# xbee_2017_v2.net
KiCad netlist of a schematic drawn in EAGLE
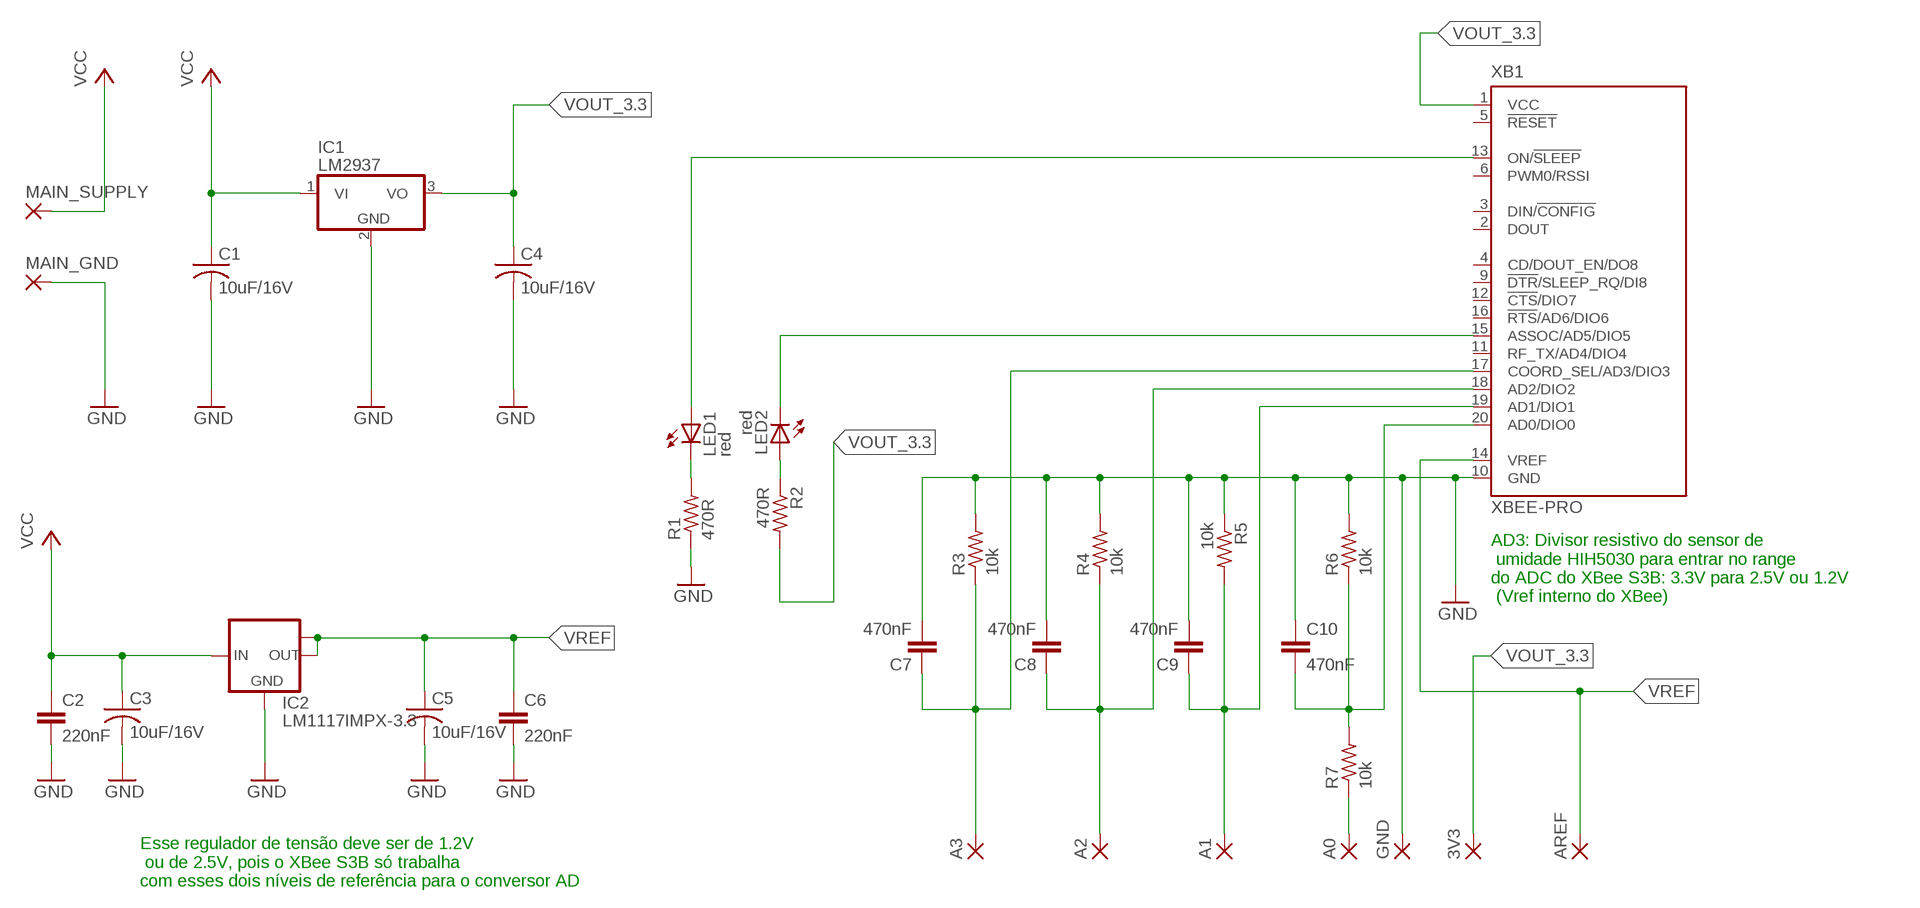
[diagram p0: schematic, sheet 1]

(export (version "E")
  (design (tool "Eeschema 10.0.6"))
  (components
    (comp (ref "3V3")
      (value "2,54/0,9")
      (footprint "eagle-import:2,54_0,9")
      (libsource (lib "eagle-import") (part "2,54/0,9"))
    )
    (comp (ref "A0")
      (value "2,54/0,9")
      (footprint "eagle-import:2,54_0,9")
      (libsource (lib "eagle-import") (part "2,54/0,9"))
    )
    (comp (ref "A1")
      (value "2,54/0,9")
      (footprint "eagle-import:2,54_0,9")
      (libsource (lib "eagle-import") (part "2,54/0,9"))
    )
    (comp (ref "A2")
      (value "2,54/0,9")
      (footprint "eagle-import:2,54_0,9")
      (libsource (lib "eagle-import") (part "2,54/0,9"))
    )
    (comp (ref "A3")
      (value "2,54/0,9")
      (footprint "eagle-import:2,54_0,9")
      (libsource (lib "eagle-import") (part "2,54/0,9"))
    )
    (comp (ref "AREF")
      (value "2,54/0,9")
      (footprint "eagle-import:2,54_0,9")
      (libsource (lib "eagle-import") (part "2,54/0,9"))
    )
    (comp (ref "C1")
      (value "10uF/16V")
      (footprint "eagle-import:C025-030X050")
      (libsource (lib "eagle-import") (part "C-US025-030X050"))
    )
    (comp (ref "C2")
      (value "220nF")
      (footprint "eagle-import:C025-025X050")
      (libsource (lib "eagle-import") (part "C-EU025-025X050"))
    )
    (comp (ref "C3")
      (value "10uF/16V")
      (footprint "eagle-import:C025-030X050")
      (libsource (lib "eagle-import") (part "C-US025-030X050"))
    )
    (comp (ref "C4")
      (value "10uF/16V")
      (footprint "eagle-import:C025-030X050")
      (libsource (lib "eagle-import") (part "C-US025-030X050"))
    )
    (comp (ref "C5")
      (value "10uF/16V")
      (footprint "eagle-import:C025-030X050")
      (libsource (lib "eagle-import") (part "C-US025-030X050"))
    )
    (comp (ref "C6")
      (value "220nF")
      (footprint "eagle-import:C025-025X050")
      (libsource (lib "eagle-import") (part "C-EU025-025X050"))
    )
    (comp (ref "C7")
      (value "470nF")
      (footprint "eagle-import:C5B2.5")
      (libsource (lib "eagle-import") (part "C5/2.5"))
    )
    (comp (ref "C8")
      (value "470nF")
      (footprint "eagle-import:C5B2.5")
      (libsource (lib "eagle-import") (part "C5/2.5"))
    )
    (comp (ref "C9")
      (value "470nF")
      (footprint "eagle-import:C5B2.5")
      (libsource (lib "eagle-import") (part "C5/2.5"))
    )
    (comp (ref "C10")
      (value "470nF")
      (footprint "eagle-import:C5B2.5")
      (libsource (lib "eagle-import") (part "C5/2.5"))
    )
    (comp (ref "GND")
      (value "2,54/0,9")
      (footprint "eagle-import:2,54_0,9")
      (libsource (lib "eagle-import") (part "2,54/0,9"))
    )
    (comp (ref "IC1")
      (value "LM2937")
      (footprint "eagle-import:TO263-3")
      (libsource (lib "eagle-import") (part "LM2937"))
    )
    (comp (ref "IC2")
      (value "LM1117IMPX-3.3")
      (footprint "eagle-import:SOT223")
      (libsource (lib "eagle-import") (part "LM1117IMPX-3.3"))
    )
    (comp (ref "LED1")
      (value "red")
      (footprint "eagle-import:LED3MM")
      (libsource (lib "eagle-import") (part "LED3MM"))
    )
    (comp (ref "LED2")
      (value "red")
      (footprint "eagle-import:LED3MM")
      (libsource (lib "eagle-import") (part "LED3MM"))
    )
    (comp (ref "MAIN_GND")
      (value "3,17/1,3")
      (footprint "eagle-import:3,17_1,3")
      (libsource (lib "eagle-import") (part "3,17/1,3"))
    )
    (comp (ref "MAIN_SUPPLY")
      (value "3,17/1,3")
      (footprint "eagle-import:3,17_1,3")
      (libsource (lib "eagle-import") (part "3,17/1,3"))
    )
    (comp (ref "R1")
      (value "470R")
      (footprint "eagle-import:0207_10")
      (libsource (lib "eagle-import") (part "R-US_0207/10"))
    )
    (comp (ref "R2")
      (value "470R")
      (footprint "eagle-import:0207_10")
      (libsource (lib "eagle-import") (part "R-US_0207/10"))
    )
    (comp (ref "R3")
      (value "10k")
      (footprint "eagle-import:0207_10")
      (libsource (lib "eagle-import") (part "R-US_0207/10"))
    )
    (comp (ref "R4")
      (value "10k")
      (footprint "eagle-import:0207_10")
      (libsource (lib "eagle-import") (part "R-US_0207/10"))
    )
    (comp (ref "R5")
      (value "10k")
      (footprint "eagle-import:0207_10")
      (libsource (lib "eagle-import") (part "R-US_0207/10"))
    )
    (comp (ref "R6")
      (value "10k")
      (footprint "eagle-import:0207_10")
      (libsource (lib "eagle-import") (part "R-US_0207/10"))
    )
    (comp (ref "R7")
      (value "10k")
      (footprint "eagle-import:0207_10")
      (libsource (lib "eagle-import") (part "R-US_0207/10"))
    )
    (comp (ref "XB1")
      (value "XBEE-PRO")
      (footprint "eagle-import:XBEE-PRO")
      (fields (field (name "MPN") "XBP24-AWI-001"))
      (libsource (lib "eagle-import") (part "XBEE-PRO"))
    )
  )
  (nets
    (net (code "1") (name "GND") (class "Default")
      (node (ref "C1") (pin "2") (pinfunction "2_2") (pintype "passive"))
      (node (ref "C10") (pin "1") (pinfunction "1_1") (pintype "passive"))
      (node (ref "C2") (pin "2") (pinfunction "2_2") (pintype "passive"))
      (node (ref "C3") (pin "2") (pinfunction "2_2") (pintype "passive"))
      (node (ref "C4") (pin "2") (pinfunction "2_2") (pintype "passive"))
      (node (ref "C5") (pin "2") (pinfunction "2_2") (pintype "passive"))
      (node (ref "C6") (pin "2") (pinfunction "2_2") (pintype "passive"))
      (node (ref "C7") (pin "2") (pinfunction "2_2") (pintype "passive"))
      (node (ref "C8") (pin "2") (pinfunction "2_2") (pintype "passive"))
      (node (ref "C9") (pin "2") (pinfunction "2_2") (pintype "passive"))
      (node (ref "GND") (pin "1") (pinfunction "P_1") (pintype "passive"))
      (node (ref "IC1") (pin "2") (pinfunction "GND_2") (pintype "passive"))
      (node (ref "IC2") (pin "1") (pinfunction "GND_1") (pintype "input"))
      (node (ref "MAIN_GND") (pin "1") (pinfunction "P_1") (pintype "passive"))
      (node (ref "R1") (pin "1") (pinfunction "1_1") (pintype "passive"))
      (node (ref "R3") (pin "2") (pinfunction "2_2") (pintype "passive"))
      (node (ref "R4") (pin "2") (pinfunction "2_2") (pintype "passive"))
      (node (ref "R5") (pin "1") (pinfunction "1_1") (pintype "passive"))
      (node (ref "R6") (pin "2") (pinfunction "2_2") (pintype "passive"))
      (node (ref "XB1") (pin "10") (pinfunction "GND_10") (pintype "power_in"))
    )
    (net (code "2") (name "Net-(A0-P)") (class "Default")
      (node (ref "A0") (pin "1") (pinfunction "P_1") (pintype "passive"))
      (node (ref "R7") (pin "1") (pinfunction "1_1") (pintype "passive"))
    )
    (net (code "3") (name "Net-(A1-P)") (class "Default")
      (node (ref "A1") (pin "1") (pinfunction "P_1") (pintype "passive"))
      (node (ref "C9") (pin "1") (pinfunction "1_1") (pintype "passive"))
      (node (ref "R5") (pin "2") (pinfunction "2_2") (pintype "passive"))
      (node (ref "XB1") (pin "19") (pinfunction "AD1/DIO1_19") (pintype "bidirectional"))
    )
    (net (code "4") (name "Net-(A2-P)") (class "Default")
      (node (ref "A2") (pin "1") (pinfunction "P_1") (pintype "passive"))
      (node (ref "C8") (pin "1") (pinfunction "1_1") (pintype "passive"))
      (node (ref "R4") (pin "1") (pinfunction "1_1") (pintype "passive"))
      (node (ref "XB1") (pin "18") (pinfunction "AD2/DIO2_18") (pintype "bidirectional"))
    )
    (net (code "5") (name "Net-(A3-P)") (class "Default")
      (node (ref "A3") (pin "1") (pinfunction "P_1") (pintype "passive"))
      (node (ref "C7") (pin "1") (pinfunction "1_1") (pintype "passive"))
      (node (ref "R3") (pin "1") (pinfunction "1_1") (pintype "passive"))
      (node (ref "XB1") (pin "17") (pinfunction "COORD_SEL/AD3/DIO3_17") (pintype "bidirectional"))
    )
    (net (code "6") (name "Net-(LED1-C)") (class "Default")
      (node (ref "LED1") (pin "K") (pinfunction "C_K") (pintype "passive"))
      (node (ref "R1") (pin "2") (pinfunction "2_2") (pintype "passive"))
    )
    (net (code "7") (name "Net-(LED2-C)") (class "Default")
      (node (ref "LED2") (pin "K") (pinfunction "C_K") (pintype "passive"))
      (node (ref "XB1") (pin "15") (pinfunction "ASSOC/AD5/DIO5_15") (pintype "bidirectional"))
    )
    (net (code "8") (name "Net-(LED2-PadA)") (class "Default")
      (node (ref "LED2") (pin "A") (pinfunction "A_A") (pintype "passive"))
      (node (ref "R2") (pin "1") (pinfunction "1_1") (pintype "passive"))
    )
    (net (code "9") (name "Net-(XB1-AD0{slash}DIO0)") (class "Default")
      (node (ref "C10") (pin "2") (pinfunction "2_2") (pintype "passive"))
      (node (ref "R6") (pin "1") (pinfunction "1_1") (pintype "passive"))
      (node (ref "R7") (pin "2") (pinfunction "2_2") (pintype "passive"))
      (node (ref "XB1") (pin "20") (pinfunction "AD0/DIO0_20") (pintype "bidirectional"))
    )
    (net (code "10") (name "Net-(XB1-ON{slash}~{SLEEP})") (class "Default")
      (node (ref "LED1") (pin "A") (pinfunction "A_A") (pintype "passive"))
      (node (ref "XB1") (pin "13") (pinfunction "ON/~{SLEEP}_13") (pintype "output"))
    )
    (net (code "11") (name "VCC") (class "Default")
      (node (ref "C1") (pin "1") (pinfunction "1_1") (pintype "passive"))
      (node (ref "C2") (pin "1") (pinfunction "1_1") (pintype "passive"))
      (node (ref "C3") (pin "1") (pinfunction "1_1") (pintype "passive"))
      (node (ref "IC1") (pin "1") (pinfunction "VI_1") (pintype "input"))
      (node (ref "IC2") (pin "3") (pinfunction "IN_3") (pintype "input"))
      (node (ref "MAIN_SUPPLY") (pin "1") (pinfunction "P_1") (pintype "passive"))
    )
    (net (code "12") (name "VOUT_3.3") (class "Default")
      (node (ref "C4") (pin "1") (pinfunction "1_1") (pintype "passive"))
      (node (ref "IC1") (pin "3") (pinfunction "VO_3") (pintype "passive"))
      (node (ref "R2") (pin "2") (pinfunction "2_2") (pintype "passive"))
      (node (ref "XB1") (pin "1") (pinfunction "VCC_1") (pintype "power_in"))
    )
    (net (code "13") (name "VREF") (class "Default")
      (node (ref "AREF") (pin "1") (pinfunction "P_1") (pintype "passive"))
      (node (ref "C5") (pin "1") (pinfunction "1_1") (pintype "passive"))
      (node (ref "C6") (pin "1") (pinfunction "1_1") (pintype "passive"))
      (node (ref "IC2") (pin "2") (pinfunction "OUT_2") (pintype "passive"))
      (node (ref "IC2") (pin "TAB") (pinfunction "OUT1_TAB") (pintype "passive"))
      (node (ref "XB1") (pin "14") (pinfunction "VREF_14") (pintype "input"))
    )
    (net (code "14") (name "unconnected-(3V3-P-Pad1)") (class "Default")
      (node (ref "3V3") (pin "1") (pinfunction "P_1") (pintype "passive"))
    )
    (net (code "15") (name "unconnected-(XB1-CD{slash}DOUT_EN{slash}DO8-Pad4)") (class "Default")
      (node (ref "XB1") (pin "4") (pinfunction "CD/DOUT_EN/DO8_4") (pintype "output"))
    )
    (net (code "16") (name "unconnected-(XB1-DIN{slash}~{CONFIG}-Pad3)") (class "Default")
      (node (ref "XB1") (pin "3") (pinfunction "DIN/~{CONFIG}_3") (pintype "input"))
    )
    (net (code "17") (name "unconnected-(XB1-DOUT-Pad2)") (class "Default")
      (node (ref "XB1") (pin "2") (pinfunction "DOUT_2") (pintype "output"))
    )
    (net (code "18") (name "unconnected-(XB1-PWM0{slash}RSSI-Pad6)") (class "Default")
      (node (ref "XB1") (pin "6") (pinfunction "PWM0/RSSI_6") (pintype "output"))
    )
    (net (code "19") (name "unconnected-(XB1-RF_TX{slash}AD4{slash}DIO4-Pad11)") (class "Default")
      (node (ref "XB1") (pin "11") (pinfunction "RF_TX/AD4/DIO4_11") (pintype "bidirectional"))
    )
    (net (code "20") (name "unconnected-(XB1-~{CTS}{slash}DIO7-Pad12)") (class "Default")
      (node (ref "XB1") (pin "12") (pinfunction "~{CTS}/DIO7_12") (pintype "bidirectional"))
    )
    (net (code "21") (name "unconnected-(XB1-~{DTR}{slash}SLEEP_RQ{slash}DI8-Pad9)") (class "Default")
      (node (ref "XB1") (pin "9") (pinfunction "~{DTR}/SLEEP_RQ/DI8_9") (pintype "bidirectional"))
    )
    (net (code "22") (name "unconnected-(XB1-~{RESET}-Pad5)") (class "Default")
      (node (ref "XB1") (pin "5") (pinfunction "~{RESET}_5") (pintype "input"))
    )
    (net (code "23") (name "unconnected-(XB1-~{RTS}{slash}AD6{slash}DIO6-Pad16)") (class "Default")
      (node (ref "XB1") (pin "16") (pinfunction "~{RTS}/AD6/DIO6_16") (pintype "bidirectional"))
    )
  )
)
